# USB2SPI.net
KiCad netlist of a schematic drawn in EAGLE
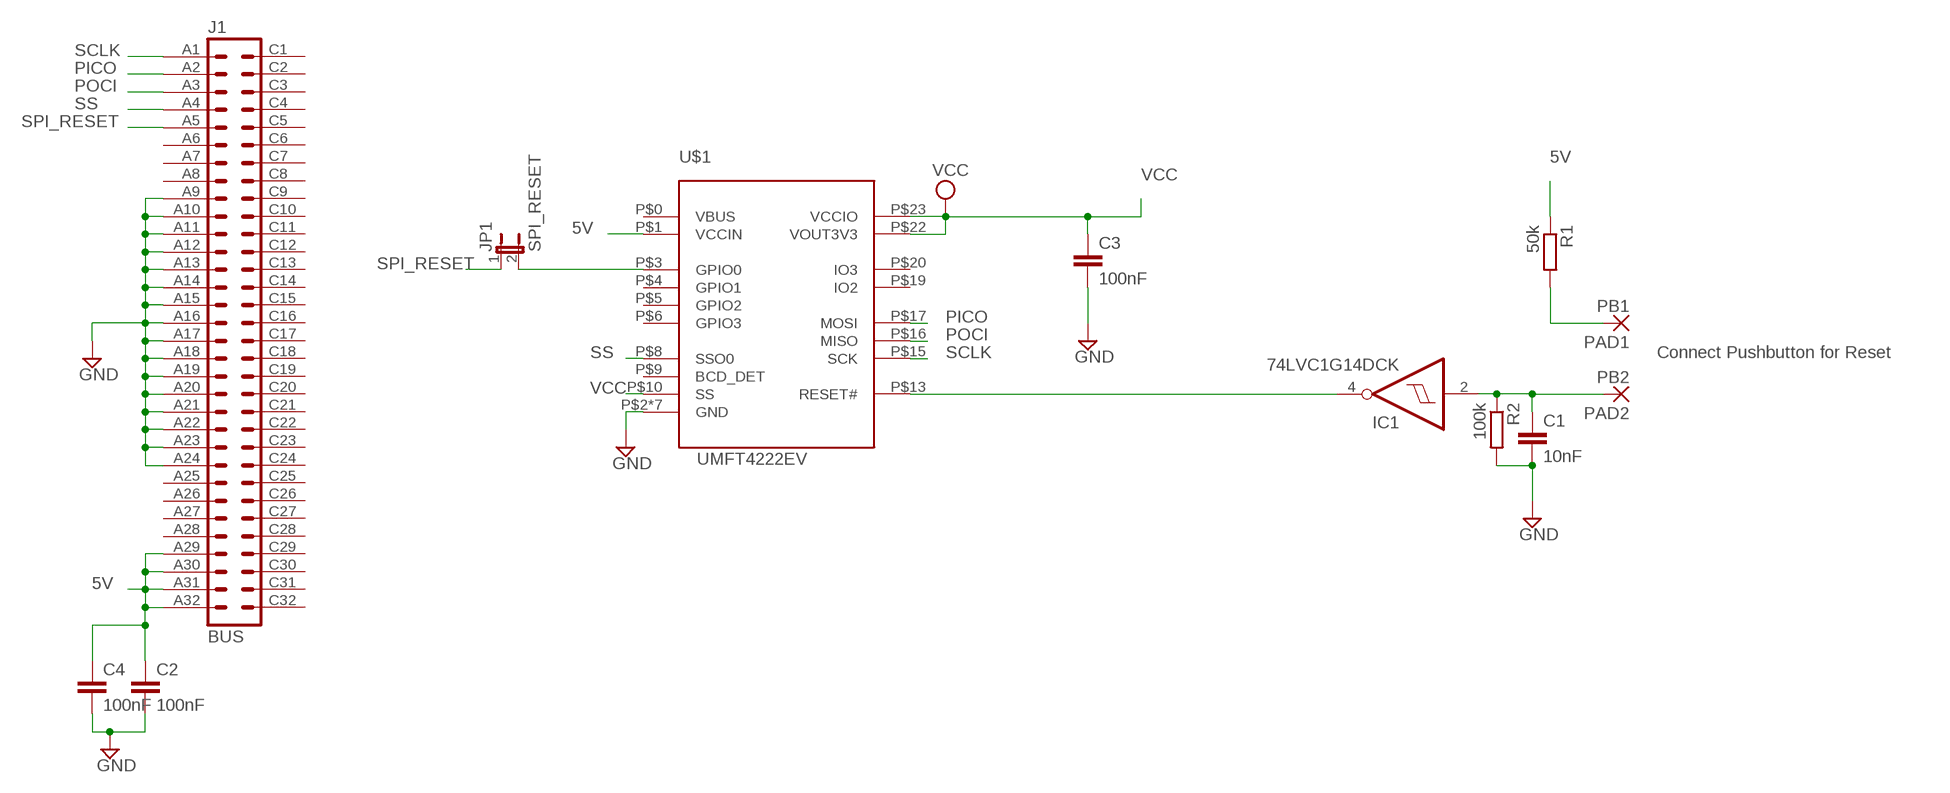
[diagram p0: schematic, sheet 1]

(export (version "E")
  (design (tool "Eeschema 10.0.6"))
  (components
    (comp (ref "C1")
      (value "10nF")
      (footprint "eagle-import:C0603")
      (libsource (lib "eagle-import") (part "C-EUC0603"))
    )
    (comp (ref "C2")
      (value "100nF")
      (footprint "eagle-import:C0603")
      (libsource (lib "eagle-import") (part "C-EUC0603"))
    )
    (comp (ref "C3")
      (value "100nF")
      (footprint "eagle-import:C0603")
      (libsource (lib "eagle-import") (part "C-EUC0603"))
    )
    (comp (ref "C4")
      (value "100nF")
      (footprint "eagle-import:C0603")
      (libsource (lib "eagle-import") (part "C-EUC0603"))
    )
    (comp (ref "IC1")
      (value "74LVC1G14DCK")
      (footprint "eagle-import:SC70-5")
      (libsource (lib "eagle-import") (part "741G14DCKLVC"))
    )
    (comp (ref "J1")
      (value "BUS")
      (footprint "eagle-import:VG64P")
      (libsource (lib "eagle-import") (part "VG64P"))
    )
    (comp (ref "JP1")
      (value "SPI_RESET")
      (footprint "eagle-import:JP1")
      (libsource (lib "eagle-import") (part "JP1E"))
    )
    (comp (ref "PAD1")
      (value "PB1")
      (footprint "eagle-import:SMD2,54-5,08")
      (libsource (lib "eagle-import") (part "SMD5"))
    )
    (comp (ref "PAD2")
      (value "PB2")
      (footprint "eagle-import:SMD2,54-5,08")
      (libsource (lib "eagle-import") (part "SMD5"))
    )
    (comp (ref "R1")
      (value "50k")
      (footprint "eagle-import:R0603")
      (libsource (lib "eagle-import") (part "R-EU_R0603"))
    )
    (comp (ref "R2")
      (value "100k")
      (footprint "eagle-import:R0603")
      (libsource (lib "eagle-import") (part "R-EU_R0603"))
    )
    (comp (ref "U$1")
      (value "UMFT4222EV")
      (footprint "eagle-import:UMFT4222EV")
      (libsource (lib "eagle-import") (part "UMFT4222EV"))
    )
  )
  (nets
    (net (code "1") (name "/5V") (class "Default")
      (node (ref "C2") (pin "1") (pinfunction "1_1") (pintype "passive"))
      (node (ref "C4") (pin "1") (pinfunction "1_1") (pintype "passive"))
      (node (ref "J1") (pin "A29") (pinfunction "A29_A29") (pintype "passive"))
      (node (ref "J1") (pin "A30") (pinfunction "A30_A30") (pintype "passive"))
      (node (ref "J1") (pin "A31") (pinfunction "A31_A31") (pintype "passive"))
      (node (ref "J1") (pin "A32") (pinfunction "A32_A32") (pintype "passive"))
      (node (ref "R1") (pin "1") (pinfunction "1_1") (pintype "passive"))
      (node (ref "U$1") (pin "P$1") (pinfunction "VCCIN_P$1") (pintype "bidirectional"))
    )
    (net (code "2") (name "/PICO") (class "Default")
      (node (ref "J1") (pin "A2") (pinfunction "A2_A2") (pintype "passive"))
      (node (ref "U$1") (pin "P$17") (pinfunction "MOSI_P$17") (pintype "bidirectional"))
    )
    (net (code "3") (name "/POCI") (class "Default")
      (node (ref "J1") (pin "A3") (pinfunction "A3_A3") (pintype "passive"))
      (node (ref "U$1") (pin "P$16") (pinfunction "MISO_P$16") (pintype "bidirectional"))
    )
    (net (code "4") (name "/SCLK") (class "Default")
      (node (ref "J1") (pin "A1") (pinfunction "A1_A1") (pintype "passive"))
      (node (ref "U$1") (pin "P$15") (pinfunction "SCK_P$15") (pintype "bidirectional"))
    )
    (net (code "5") (name "/SPI_RESET") (class "Default")
      (node (ref "J1") (pin "A5") (pinfunction "A5_A5") (pintype "passive"))
      (node (ref "JP1") (pin "1") (pinfunction "1_1") (pintype "passive"))
    )
    (net (code "6") (name "/SS") (class "Default")
      (node (ref "J1") (pin "A4") (pinfunction "A4_A4") (pintype "passive"))
      (node (ref "U$1") (pin "P$8") (pinfunction "SSO0_P$8") (pintype "bidirectional"))
    )
    (net (code "7") (name "GND") (class "Default")
      (node (ref "C1") (pin "2") (pinfunction "2_2") (pintype "passive"))
      (node (ref "C2") (pin "2") (pinfunction "2_2") (pintype "passive"))
      (node (ref "C3") (pin "2") (pinfunction "2_2") (pintype "passive"))
      (node (ref "C4") (pin "2") (pinfunction "2_2") (pintype "passive"))
      (node (ref "J1") (pin "A10") (pinfunction "A10_A10") (pintype "passive"))
      (node (ref "J1") (pin "A11") (pinfunction "A11_A11") (pintype "passive"))
      (node (ref "J1") (pin "A12") (pinfunction "A12_A12") (pintype "passive"))
      (node (ref "J1") (pin "A13") (pinfunction "A13_A13") (pintype "passive"))
      (node (ref "J1") (pin "A14") (pinfunction "A14_A14") (pintype "passive"))
      (node (ref "J1") (pin "A15") (pinfunction "A15_A15") (pintype "passive"))
      (node (ref "J1") (pin "A16") (pinfunction "A16_A16") (pintype "passive"))
      (node (ref "J1") (pin "A17") (pinfunction "A17_A17") (pintype "passive"))
      (node (ref "J1") (pin "A18") (pinfunction "A18_A18") (pintype "passive"))
      (node (ref "J1") (pin "A19") (pinfunction "A19_A19") (pintype "passive"))
      (node (ref "J1") (pin "A20") (pinfunction "A20_A20") (pintype "passive"))
      (node (ref "J1") (pin "A21") (pinfunction "A21_A21") (pintype "passive"))
      (node (ref "J1") (pin "A22") (pinfunction "A22_A22") (pintype "passive"))
      (node (ref "J1") (pin "A23") (pinfunction "A23_A23") (pintype "passive"))
      (node (ref "J1") (pin "A24") (pinfunction "A24_A24") (pintype "passive"))
      (node (ref "J1") (pin "A9") (pinfunction "A9_A9") (pintype "passive"))
      (node (ref "R2") (pin "2") (pinfunction "2_2") (pintype "passive"))
      (node (ref "U$1") (pin "P$11") (pinfunction "GND_P$11") (pintype "bidirectional"))
      (node (ref "U$1") (pin "P$12") (pinfunction "GND_P$12") (pintype "bidirectional"))
      (node (ref "U$1") (pin "P$14") (pinfunction "GND_P$14") (pintype "bidirectional"))
      (node (ref "U$1") (pin "P$18") (pinfunction "GND_P$18") (pintype "bidirectional"))
      (node (ref "U$1") (pin "P$2") (pinfunction "GND_P$2") (pintype "bidirectional"))
      (node (ref "U$1") (pin "P$21") (pinfunction "GND_P$21") (pintype "bidirectional"))
      (node (ref "U$1") (pin "P$7") (pinfunction "GND_P$7") (pintype "bidirectional"))
    )
    (net (code "8") (name "Net-(IC1A-I)") (class "Default")
      (node (ref "C1") (pin "1") (pinfunction "1_1") (pintype "passive"))
      (node (ref "IC1") (pin "2") (pinfunction "I_2") (pintype "input"))
      (node (ref "PAD2") (pin "1") (pinfunction "P_1") (pintype "passive"))
      (node (ref "R2") (pin "1") (pinfunction "1_1") (pintype "passive"))
    )
    (net (code "9") (name "Net-(IC1A-O)") (class "Default")
      (node (ref "IC1") (pin "4") (pinfunction "O_4") (pintype "output"))
      (node (ref "U$1") (pin "P$13") (pinfunction "RESET#_P$13") (pintype "bidirectional"))
    )
    (net (code "10") (name "Net-(PAD1-P)") (class "Default")
      (node (ref "PAD1") (pin "1") (pinfunction "P_1") (pintype "passive"))
      (node (ref "R1") (pin "2") (pinfunction "2_2") (pintype "passive"))
    )
    (net (code "11") (name "Net-(U$1-GPIO0)") (class "Default")
      (node (ref "JP1") (pin "2") (pinfunction "2_2") (pintype "passive"))
      (node (ref "U$1") (pin "P$3") (pinfunction "GPIO0_P$3") (pintype "bidirectional"))
    )
    (net (code "12") (name "VCC") (class "Default")
      (node (ref "C3") (pin "1") (pinfunction "1_1") (pintype "passive"))
      (node (ref "U$1") (pin "P$10") (pinfunction "SS_P$10") (pintype "bidirectional"))
      (node (ref "U$1") (pin "P$22") (pinfunction "VOUT3V3_P$22") (pintype "bidirectional"))
      (node (ref "U$1") (pin "P$23") (pinfunction "VCCIO_P$23") (pintype "bidirectional"))
    )
    (net (code "13") (name "unconnected-(J1-PadA6)") (class "Default")
      (node (ref "J1") (pin "A6") (pinfunction "A6_A6") (pintype "passive"))
    )
    (net (code "14") (name "unconnected-(J1-PadA7)") (class "Default")
      (node (ref "J1") (pin "A7") (pinfunction "A7_A7") (pintype "passive"))
    )
    (net (code "15") (name "unconnected-(J1-PadA8)") (class "Default")
      (node (ref "J1") (pin "A8") (pinfunction "A8_A8") (pintype "passive"))
    )
    (net (code "16") (name "unconnected-(J1-PadA25)") (class "Default")
      (node (ref "J1") (pin "A25") (pinfunction "A25_A25") (pintype "passive"))
    )
    (net (code "17") (name "unconnected-(J1-PadA26)") (class "Default")
      (node (ref "J1") (pin "A26") (pinfunction "A26_A26") (pintype "passive"))
    )
    (net (code "18") (name "unconnected-(J1-PadA27)") (class "Default")
      (node (ref "J1") (pin "A27") (pinfunction "A27_A27") (pintype "passive"))
    )
    (net (code "19") (name "unconnected-(J1-PadA28)") (class "Default")
      (node (ref "J1") (pin "A28") (pinfunction "A28_A28") (pintype "passive"))
    )
    (net (code "20") (name "unconnected-(J1-PadC1)") (class "Default")
      (node (ref "J1") (pin "C1") (pinfunction "C1_C1") (pintype "passive"))
    )
    (net (code "21") (name "unconnected-(J1-PadC2)") (class "Default")
      (node (ref "J1") (pin "C2") (pinfunction "C2_C2") (pintype "passive"))
    )
    (net (code "22") (name "unconnected-(J1-PadC3)") (class "Default")
      (node (ref "J1") (pin "C3") (pinfunction "C3_C3") (pintype "passive"))
    )
    (net (code "23") (name "unconnected-(J1-PadC4)") (class "Default")
      (node (ref "J1") (pin "C4") (pinfunction "C4_C4") (pintype "passive"))
    )
    (net (code "24") (name "unconnected-(J1-PadC5)") (class "Default")
      (node (ref "J1") (pin "C5") (pinfunction "C5_C5") (pintype "passive"))
    )
    (net (code "25") (name "unconnected-(J1-PadC6)") (class "Default")
      (node (ref "J1") (pin "C6") (pinfunction "C6_C6") (pintype "passive"))
    )
    (net (code "26") (name "unconnected-(J1-PadC7)") (class "Default")
      (node (ref "J1") (pin "C7") (pinfunction "C7_C7") (pintype "passive"))
    )
    (net (code "27") (name "unconnected-(J1-PadC8)") (class "Default")
      (node (ref "J1") (pin "C8") (pinfunction "C8_C8") (pintype "passive"))
    )
    (net (code "28") (name "unconnected-(J1-PadC9)") (class "Default")
      (node (ref "J1") (pin "C9") (pinfunction "C9_C9") (pintype "passive"))
    )
    (net (code "29") (name "unconnected-(J1-PadC10)") (class "Default")
      (node (ref "J1") (pin "C10") (pinfunction "C10_C10") (pintype "passive"))
    )
    (net (code "30") (name "unconnected-(J1-PadC11)") (class "Default")
      (node (ref "J1") (pin "C11") (pinfunction "C11_C11") (pintype "passive"))
    )
    (net (code "31") (name "unconnected-(J1-PadC12)") (class "Default")
      (node (ref "J1") (pin "C12") (pinfunction "C12_C12") (pintype "passive"))
    )
    (net (code "32") (name "unconnected-(J1-PadC13)") (class "Default")
      (node (ref "J1") (pin "C13") (pinfunction "C13_C13") (pintype "passive"))
    )
    (net (code "33") (name "unconnected-(J1-PadC14)") (class "Default")
      (node (ref "J1") (pin "C14") (pinfunction "C14_C14") (pintype "passive"))
    )
    (net (code "34") (name "unconnected-(J1-PadC15)") (class "Default")
      (node (ref "J1") (pin "C15") (pinfunction "C15_C15") (pintype "passive"))
    )
    (net (code "35") (name "unconnected-(J1-PadC16)") (class "Default")
      (node (ref "J1") (pin "C16") (pinfunction "C16_C16") (pintype "passive"))
    )
    (net (code "36") (name "unconnected-(J1-PadC17)") (class "Default")
      (node (ref "J1") (pin "C17") (pinfunction "C17_C17") (pintype "passive"))
    )
    (net (code "37") (name "unconnected-(J1-PadC18)") (class "Default")
      (node (ref "J1") (pin "C18") (pinfunction "C18_C18") (pintype "passive"))
    )
    (net (code "38") (name "unconnected-(J1-PadC19)") (class "Default")
      (node (ref "J1") (pin "C19") (pinfunction "C19_C19") (pintype "passive"))
    )
    (net (code "39") (name "unconnected-(J1-PadC20)") (class "Default")
      (node (ref "J1") (pin "C20") (pinfunction "C20_C20") (pintype "passive"))
    )
    (net (code "40") (name "unconnected-(J1-PadC21)") (class "Default")
      (node (ref "J1") (pin "C21") (pinfunction "C21_C21") (pintype "passive"))
    )
    (net (code "41") (name "unconnected-(J1-PadC22)") (class "Default")
      (node (ref "J1") (pin "C22") (pinfunction "C22_C22") (pintype "passive"))
    )
    (net (code "42") (name "unconnected-(J1-PadC23)") (class "Default")
      (node (ref "J1") (pin "C23") (pinfunction "C23_C23") (pintype "passive"))
    )
    (net (code "43") (name "unconnected-(J1-PadC24)") (class "Default")
      (node (ref "J1") (pin "C24") (pinfunction "C24_C24") (pintype "passive"))
    )
    (net (code "44") (name "unconnected-(J1-PadC25)") (class "Default")
      (node (ref "J1") (pin "C25") (pinfunction "C25_C25") (pintype "passive"))
    )
    (net (code "45") (name "unconnected-(J1-PadC26)") (class "Default")
      (node (ref "J1") (pin "C26") (pinfunction "C26_C26") (pintype "passive"))
    )
    (net (code "46") (name "unconnected-(J1-PadC27)") (class "Default")
      (node (ref "J1") (pin "C27") (pinfunction "C27_C27") (pintype "passive"))
    )
    (net (code "47") (name "unconnected-(J1-PadC28)") (class "Default")
      (node (ref "J1") (pin "C28") (pinfunction "C28_C28") (pintype "passive"))
    )
    (net (code "48") (name "unconnected-(J1-PadC29)") (class "Default")
      (node (ref "J1") (pin "C29") (pinfunction "C29_C29") (pintype "passive"))
    )
    (net (code "49") (name "unconnected-(J1-PadC30)") (class "Default")
      (node (ref "J1") (pin "C30") (pinfunction "C30_C30") (pintype "passive"))
    )
    (net (code "50") (name "unconnected-(J1-PadC31)") (class "Default")
      (node (ref "J1") (pin "C31") (pinfunction "C31_C31") (pintype "passive"))
    )
    (net (code "51") (name "unconnected-(J1-PadC32)") (class "Default")
      (node (ref "J1") (pin "C32") (pinfunction "C32_C32") (pintype "passive"))
    )
    (net (code "52") (name "unconnected-(U$1-BCD_DET-PadP$9)") (class "Default")
      (node (ref "U$1") (pin "P$9") (pinfunction "BCD_DET_P$9") (pintype "bidirectional"))
    )
    (net (code "53") (name "unconnected-(U$1-GPIO1-PadP$4)") (class "Default")
      (node (ref "U$1") (pin "P$4") (pinfunction "GPIO1_P$4") (pintype "bidirectional"))
    )
    (net (code "54") (name "unconnected-(U$1-GPIO2-PadP$5)") (class "Default")
      (node (ref "U$1") (pin "P$5") (pinfunction "GPIO2_P$5") (pintype "bidirectional"))
    )
    (net (code "55") (name "unconnected-(U$1-GPIO3-PadP$6)") (class "Default")
      (node (ref "U$1") (pin "P$6") (pinfunction "GPIO3_P$6") (pintype "bidirectional"))
    )
    (net (code "56") (name "unconnected-(U$1-IO2-PadP$19)") (class "Default")
      (node (ref "U$1") (pin "P$19") (pinfunction "IO2_P$19") (pintype "bidirectional"))
    )
    (net (code "57") (name "unconnected-(U$1-IO3-PadP$20)") (class "Default")
      (node (ref "U$1") (pin "P$20") (pinfunction "IO3_P$20") (pintype "bidirectional"))
    )
    (net (code "58") (name "unconnected-(U$1-VBUS-PadP$0)") (class "Default")
      (node (ref "U$1") (pin "P$0") (pinfunction "VBUS_P$0") (pintype "bidirectional"))
    )
  )
)
